# Bridge_PCA9517.net
KiCad netlist of a schematic drawn in EAGLE
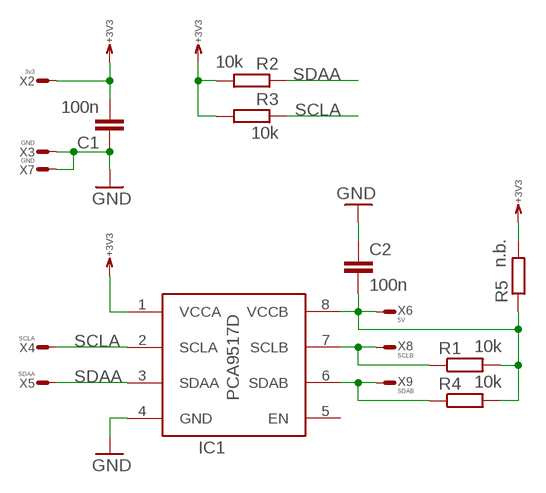
[diagram p0: schematic, sheet 1]

(export (version "E")
  (design (tool "Eeschema 10.0.6"))
  (components
    (comp (ref "C1")
      (value "100n")
      (footprint "eagle-import:0603")
      (libsource (lib "eagle-import") (part "C0603"))
    )
    (comp (ref "C2")
      (value "100n")
      (footprint "eagle-import:0603")
      (libsource (lib "eagle-import") (part "C0603"))
    )
    (comp (ref "IC1")
      (value "PCA9517D")
      (footprint "eagle-import:SOIC8")
      (libsource (lib "eagle-import") (part "PCA9517D"))
    )
    (comp (ref "R1")
      (value "10k")
      (footprint "eagle-import:0603")
      (libsource (lib "eagle-import") (part "R0603"))
    )
    (comp (ref "R2")
      (value "10k")
      (footprint "eagle-import:0603")
      (libsource (lib "eagle-import") (part "R0603"))
    )
    (comp (ref "R3")
      (value "10k")
      (footprint "eagle-import:0603")
      (libsource (lib "eagle-import") (part "R0603"))
    )
    (comp (ref "R4")
      (value "10k")
      (footprint "eagle-import:0603")
      (libsource (lib "eagle-import") (part "R0603"))
    )
    (comp (ref "R5")
      (value "n.b.")
      (footprint "eagle-import:0603")
      (libsource (lib "eagle-import") (part "R0603"))
    )
    (comp (ref "X2")
      (value "3v3")
      (footprint "eagle-import:T1.6_0.9")
      (libsource (lib "eagle-import") (part "WIREPADT1.6/0.9"))
    )
    (comp (ref "X3")
      (value "GND")
      (footprint "eagle-import:T1.6_0.9")
      (libsource (lib "eagle-import") (part "WIREPADT1.6/0.9"))
    )
    (comp (ref "X4")
      (value "SCLA")
      (footprint "eagle-import:T1.6_0.9")
      (libsource (lib "eagle-import") (part "WIREPADT1.6/0.9"))
    )
    (comp (ref "X5")
      (value "SDAA")
      (footprint "eagle-import:T1.6_0.9")
      (libsource (lib "eagle-import") (part "WIREPADT1.6/0.9"))
    )
    (comp (ref "X6")
      (value "5V")
      (footprint "eagle-import:T1.6_0.9")
      (libsource (lib "eagle-import") (part "WIREPADT1.6/0.9"))
    )
    (comp (ref "X7")
      (value "GND")
      (footprint "eagle-import:T1.6_0.9")
      (libsource (lib "eagle-import") (part "WIREPADT1.6/0.9"))
    )
    (comp (ref "X8")
      (value "SCLB")
      (footprint "eagle-import:T1.6_0.9")
      (libsource (lib "eagle-import") (part "WIREPADT1.6/0.9"))
    )
    (comp (ref "X9")
      (value "SDAB")
      (footprint "eagle-import:T1.6_0.9")
      (libsource (lib "eagle-import") (part "WIREPADT1.6/0.9"))
    )
  )
  (nets
    (net (code "1") (name "+3V3") (class "Default")
      (node (ref "C1") (pin "2") (pinfunction "2_2") (pintype "passive"))
      (node (ref "IC1") (pin "1") (pinfunction "VCCA_1") (pintype "bidirectional"))
      (node (ref "R2") (pin "2") (pinfunction "2_2") (pintype "passive"))
      (node (ref "R3") (pin "2") (pinfunction "2_2") (pintype "passive"))
      (node (ref "R5") (pin "2") (pinfunction "2_2") (pintype "passive"))
      (node (ref "X2") (pin "1") (pinfunction "S_1") (pintype "passive"))
    )
    (net (code "2") (name "/SCLA") (class "Default")
      (node (ref "IC1") (pin "2") (pinfunction "SCLA_2") (pintype "bidirectional"))
      (node (ref "R3") (pin "1") (pinfunction "1_1") (pintype "passive"))
      (node (ref "X4") (pin "1") (pinfunction "S_1") (pintype "passive"))
    )
    (net (code "3") (name "/SDAA") (class "Default")
      (node (ref "IC1") (pin "3") (pinfunction "SDAA_3") (pintype "bidirectional"))
      (node (ref "R2") (pin "1") (pinfunction "1_1") (pintype "passive"))
      (node (ref "X5") (pin "1") (pinfunction "S_1") (pintype "passive"))
    )
    (net (code "4") (name "GND") (class "Default")
      (node (ref "C1") (pin "1") (pinfunction "1_1") (pintype "passive"))
      (node (ref "C2") (pin "1") (pinfunction "1_1") (pintype "passive"))
      (node (ref "IC1") (pin "4") (pinfunction "GND_4") (pintype "bidirectional"))
      (node (ref "X3") (pin "1") (pinfunction "S_1") (pintype "passive"))
      (node (ref "X7") (pin "1") (pinfunction "S_1") (pintype "passive"))
    )
    (net (code "5") (name "Net-(IC1-SCLB)") (class "Default")
      (node (ref "IC1") (pin "7") (pinfunction "SCLB_7") (pintype "bidirectional"))
      (node (ref "R1") (pin "1") (pinfunction "1_1") (pintype "passive"))
      (node (ref "X8") (pin "1") (pinfunction "S_1") (pintype "passive"))
    )
    (net (code "6") (name "Net-(IC1-SDAB)") (class "Default")
      (node (ref "IC1") (pin "6") (pinfunction "SDAB_6") (pintype "bidirectional"))
      (node (ref "R4") (pin "1") (pinfunction "1_1") (pintype "passive"))
      (node (ref "X9") (pin "1") (pinfunction "S_1") (pintype "passive"))
    )
    (net (code "7") (name "Net-(IC1-VCCB)") (class "Default")
      (node (ref "C2") (pin "2") (pinfunction "2_2") (pintype "passive"))
      (node (ref "IC1") (pin "8") (pinfunction "VCCB_8") (pintype "bidirectional"))
      (node (ref "R1") (pin "2") (pinfunction "2_2") (pintype "passive"))
      (node (ref "R4") (pin "2") (pinfunction "2_2") (pintype "passive"))
      (node (ref "R5") (pin "1") (pinfunction "1_1") (pintype "passive"))
      (node (ref "X6") (pin "1") (pinfunction "S_1") (pintype "passive"))
    )
    (net (code "8") (name "unconnected-(IC1-EN-Pad5)") (class "Default")
      (node (ref "IC1") (pin "5") (pinfunction "EN_5") (pintype "bidirectional"))
    )
  )
)
